# untitled.net
KiCad netlist of a schematic drawn in EAGLE
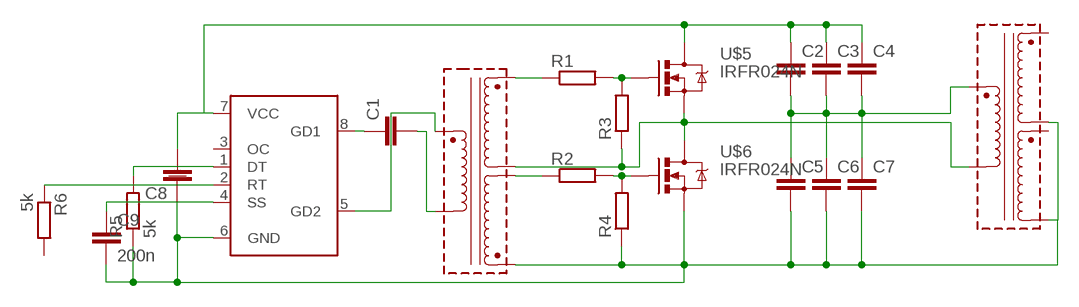
[diagram p0: schematic, sheet 1]

(export (version "E")
  (design (tool "Eeschema 10.0.6"))
  (components
    (comp (ref "C1")
      (value "CC0805")
      (footprint "eagle-import:C0805")
      (libsource (lib "eagle-import") (part "CC0805"))
    )
    (comp (ref "C2")
      (value "CC0805")
      (footprint "eagle-import:C0805")
      (libsource (lib "eagle-import") (part "CC0805"))
    )
    (comp (ref "C3")
      (value "CC0805")
      (footprint "eagle-import:C0805")
      (libsource (lib "eagle-import") (part "CC0805"))
    )
    (comp (ref "C4")
      (value "CC0805")
      (footprint "eagle-import:C0805")
      (libsource (lib "eagle-import") (part "CC0805"))
    )
    (comp (ref "C5")
      (value "CC0805")
      (footprint "eagle-import:C0805")
      (libsource (lib "eagle-import") (part "CC0805"))
    )
    (comp (ref "C6")
      (value "CC0805")
      (footprint "eagle-import:C0805")
      (libsource (lib "eagle-import") (part "CC0805"))
    )
    (comp (ref "C7")
      (value "CC0805")
      (footprint "eagle-import:C0805")
      (libsource (lib "eagle-import") (part "CC0805"))
    )
    (comp (ref "C8")
      (value "CC0805")
      (footprint "eagle-import:C0805")
      (libsource (lib "eagle-import") (part "CC0805"))
    )
    (comp (ref "C9")
      (value "200n")
      (footprint "eagle-import:C0805")
      (libsource (lib "eagle-import") (part "CC0805"))
    )
    (comp (ref "R1")
      (value "R0805")
      (footprint "eagle-import:R0805")
      (libsource (lib "eagle-import") (part "R0805"))
    )
    (comp (ref "R2")
      (value "R0805")
      (footprint "eagle-import:R0805")
      (libsource (lib "eagle-import") (part "R0805"))
    )
    (comp (ref "R3")
      (value "R0805")
      (footprint "eagle-import:R0805")
      (libsource (lib "eagle-import") (part "R0805"))
    )
    (comp (ref "R4")
      (value "R0805")
      (footprint "eagle-import:R0805")
      (libsource (lib "eagle-import") (part "R0805"))
    )
    (comp (ref "R5")
      (value "5k")
      (footprint "eagle-import:R0805")
      (libsource (lib "eagle-import") (part "R0805"))
    )
    (comp (ref "R6")
      (value "5k")
      (footprint "eagle-import:R0805")
      (libsource (lib "eagle-import") (part "R0805"))
    )
    (comp (ref "U$1")
      (value "TPS92020")
      (footprint "eagle-import:SO08")
      (libsource (lib "eagle-import") (part "TPS92020"))
    )
    (comp (ref "U$2")
      (value "ADSL_GDT")
      (footprint "eagle-import:ADSL_GDT")
      (libsource (lib "eagle-import") (part "ADSL_GDT"))
    )
    (comp (ref "U$3")
      (value "CCFL")
      (footprint "eagle-import:TRANSFORMER_HVX2")
      (libsource (lib "eagle-import") (part "CCFL"))
    )
    (comp (ref "U$5")
      (value "IRFR024N")
      (footprint "eagle-import:D-PAK_TO252AA")
      (libsource (lib "eagle-import") (part "IRFR024N"))
    )
    (comp (ref "U$6")
      (value "IRFR024N")
      (footprint "eagle-import:D-PAK_TO252AA")
      (libsource (lib "eagle-import") (part "IRFR024N"))
    )
  )
  (nets
    (net (code "1") (name "Net-(U$1-DT)") (class "Default")
      (node (ref "R5") (pin "2") (pinfunction "2_2") (pintype "passive"))
      (node (ref "U$1") (pin "1") (pinfunction "DT_1") (pintype "bidirectional"))
    )
    (net (code "2") (name "Net-(U$1-GD1)") (class "Default")
      (node (ref "C1") (pin "1") (pinfunction "1_1") (pintype "passive"))
      (node (ref "U$1") (pin "8") (pinfunction "GD1_8") (pintype "bidirectional"))
    )
    (net (code "3") (name "Net-(U$1-GD2)") (class "Default")
      (node (ref "U$1") (pin "5") (pinfunction "GD2_5") (pintype "bidirectional"))
      (node (ref "U$2") (pin "GD") (pinfunction "GD1_GD") (pintype "bidirectional"))
    )
    (net (code "4") (name "Net-(U$1-GND)") (class "Default")
      (node (ref "C5") (pin "2") (pinfunction "2_2") (pintype "passive"))
      (node (ref "C6") (pin "2") (pinfunction "2_2") (pintype "passive"))
      (node (ref "C7") (pin "2") (pinfunction "2_2") (pintype "passive"))
      (node (ref "C8") (pin "1") (pinfunction "1_1") (pintype "passive"))
      (node (ref "C9") (pin "2") (pinfunction "2_2") (pintype "passive"))
      (node (ref "R4") (pin "1") (pinfunction "1_1") (pintype "passive"))
      (node (ref "R5") (pin "1") (pinfunction "1_1") (pintype "passive"))
      (node (ref "U$1") (pin "6") (pinfunction "GND_6") (pintype "bidirectional"))
      (node (ref "U$2") (pin "OUT2") (pinfunction "OUT2+_OUT2") (pintype "bidirectional"))
      (node (ref "U$3") (pin "P$6") (pinfunction "OUT1-_P$6") (pintype "bidirectional"))
      (node (ref "U$3") (pin "P$7") (pinfunction "OUT2+_P$7") (pintype "bidirectional"))
      (node (ref "U$6") (pin "3") (pinfunction "S_3") (pintype "passive"))
    )
    (net (code "5") (name "Net-(U$1-RT)") (class "Default")
      (node (ref "R6") (pin "1") (pinfunction "1_1") (pintype "passive"))
      (node (ref "U$1") (pin "2") (pinfunction "RT_2") (pintype "bidirectional"))
    )
    (net (code "6") (name "Net-(U$1-SS)") (class "Default")
      (node (ref "C9") (pin "1") (pinfunction "1_1") (pintype "passive"))
      (node (ref "U$1") (pin "4") (pinfunction "SS_4") (pintype "bidirectional"))
    )
    (net (code "7") (name "Net-(U$1-VCC)") (class "Default")
      (node (ref "C2") (pin "1") (pinfunction "1_1") (pintype "passive"))
      (node (ref "C3") (pin "1") (pinfunction "1_1") (pintype "passive"))
      (node (ref "C4") (pin "1") (pinfunction "1_1") (pintype "passive"))
      (node (ref "C8") (pin "2") (pinfunction "2_2") (pintype "passive"))
      (node (ref "U$1") (pin "7") (pinfunction "VCC_7") (pintype "bidirectional"))
      (node (ref "U$5") (pin "2") (pinfunction "D_2") (pintype "passive"))
    )
    (net (code "8") (name "Net-(U$2-GD2)") (class "Default")
      (node (ref "C1") (pin "2") (pinfunction "2_2") (pintype "passive"))
      (node (ref "U$2") (pin "GD`") (pinfunction "GD2_GD`") (pintype "bidirectional"))
    )
    (net (code "9") (name "Net-(U$2-OUT1+)") (class "Default")
      (node (ref "R1") (pin "1") (pinfunction "1_1") (pintype "passive"))
      (node (ref "U$2") (pin "OUT1") (pinfunction "OUT1+_OUT1") (pintype "bidirectional"))
    )
    (net (code "10") (name "Net-(U$2-OUT1-)") (class "Default")
      (node (ref "R3") (pin "1") (pinfunction "1_1") (pintype "passive"))
      (node (ref "U$2") (pin "OUT1`") (pinfunction "OUT1-_OUT1`") (pintype "bidirectional"))
      (node (ref "U$3") (pin "P$3") (pinfunction "GD2_P$3") (pintype "bidirectional"))
      (node (ref "U$5") (pin "3") (pinfunction "S_3") (pintype "passive"))
      (node (ref "U$6") (pin "2") (pinfunction "D_2") (pintype "passive"))
    )
    (net (code "11") (name "Net-(U$2-OUT2-)") (class "Default")
      (node (ref "R2") (pin "1") (pinfunction "1_1") (pintype "passive"))
      (node (ref "U$2") (pin "OUT2`") (pinfunction "OUT2-_OUT2`") (pintype "bidirectional"))
    )
    (net (code "12") (name "Net-(U$3-GD1)") (class "Default")
      (node (ref "C2") (pin "2") (pinfunction "2_2") (pintype "passive"))
      (node (ref "C3") (pin "2") (pinfunction "2_2") (pintype "passive"))
      (node (ref "C4") (pin "2") (pinfunction "2_2") (pintype "passive"))
      (node (ref "C5") (pin "1") (pinfunction "1_1") (pintype "passive"))
      (node (ref "C6") (pin "1") (pinfunction "1_1") (pintype "passive"))
      (node (ref "C7") (pin "1") (pinfunction "1_1") (pintype "passive"))
      (node (ref "U$3") (pin "P$2") (pinfunction "GD1_P$2") (pintype "bidirectional"))
    )
    (net (code "13") (name "Net-(U$5-G)") (class "Default")
      (node (ref "R1") (pin "2") (pinfunction "2_2") (pintype "passive"))
      (node (ref "R3") (pin "2") (pinfunction "2_2") (pintype "passive"))
      (node (ref "U$5") (pin "1") (pinfunction "G_1") (pintype "passive"))
    )
    (net (code "14") (name "Net-(U$6-G)") (class "Default")
      (node (ref "R2") (pin "2") (pinfunction "2_2") (pintype "passive"))
      (node (ref "R4") (pin "2") (pinfunction "2_2") (pintype "passive"))
      (node (ref "U$6") (pin "1") (pinfunction "G_1") (pintype "passive"))
    )
    (net (code "15") (name "unconnected-(R6-Pad2)") (class "Default")
      (node (ref "R6") (pin "2") (pinfunction "2_2") (pintype "passive"))
    )
    (net (code "16") (name "unconnected-(U$1-OC-Pad3)") (class "Default")
      (node (ref "U$1") (pin "3") (pinfunction "OC_3") (pintype "bidirectional"))
    )
    (net (code "17") (name "unconnected-(U$3-OUT1+-PadP$5)") (class "Default")
      (node (ref "U$3") (pin "P$5") (pinfunction "OUT1+_P$5") (pintype "bidirectional"))
    )
    (net (code "18") (name "unconnected-(U$3-OUT2--PadP$8)") (class "Default")
      (node (ref "U$3") (pin "P$8") (pinfunction "OUT2-_P$8") (pintype "bidirectional"))
    )
  )
)
